# DS_PLUS1.net
KiCad netlist of a schematic drawn in EAGLE
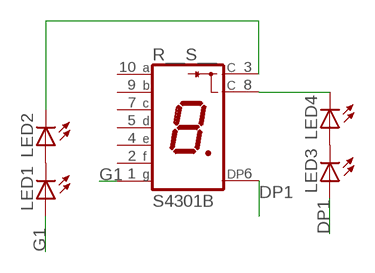
[diagram p0: schematic, sheet 1]

(export (version "E")
  (design (tool "Eeschema 10.0.6"))
  (components
    (comp (ref "LED1")
      (value "LEDCHIP-LED0603")
      (footprint "eagle-import:CHIP-LED0603")
      (libsource (lib "eagle-import") (part "LEDCHIP-LED0603"))
    )
    (comp (ref "LED2")
      (value "LEDCHIP-LED0603")
      (footprint "eagle-import:CHIP-LED0603")
      (libsource (lib "eagle-import") (part "LEDCHIP-LED0603"))
    )
    (comp (ref "LED3")
      (value "LEDCHIP-LED0603")
      (footprint "eagle-import:CHIP-LED0603")
      (libsource (lib "eagle-import") (part "LEDCHIP-LED0603"))
    )
    (comp (ref "LED4")
      (value "LEDCHIP-LED0603")
      (footprint "eagle-import:CHIP-LED0603")
      (libsource (lib "eagle-import") (part "LEDCHIP-LED0603"))
    )
    (comp (ref "R__S__")
      (value "S4301B")
      (footprint "eagle-import:S4301B")
      (libsource (lib "eagle-import") (part "S4301B"))
    )
  )
  (nets
    (net (code "1") (name "/DP1") (class "Default")
      (node (ref "LED3") (pin "A") (pinfunction "A_A") (pintype "passive"))
      (node (ref "R__S__") (pin "6") (pinfunction "DP_6") (pintype "passive"))
    )
    (net (code "2") (name "/G1") (class "Default")
      (node (ref "LED1") (pin "A") (pinfunction "A_A") (pintype "passive"))
      (node (ref "R__S__") (pin "1") (pinfunction "G_1") (pintype "passive"))
    )
    (net (code "3") (name "Net-(LED1-PadC)") (class "Default")
      (node (ref "LED1") (pin "C") (pinfunction "C_C") (pintype "passive"))
      (node (ref "LED2") (pin "A") (pinfunction "A_A") (pintype "passive"))
    )
    (net (code "4") (name "Net-(LED2-PadC)") (class "Default")
      (node (ref "LED2") (pin "C") (pinfunction "C_C") (pintype "passive"))
      (node (ref "R__S__") (pin "3") (pinfunction "C_3") (pintype "passive"))
    )
    (net (code "5") (name "Net-(LED3-PadC)") (class "Default")
      (node (ref "LED3") (pin "C") (pinfunction "C_C") (pintype "passive"))
      (node (ref "LED4") (pin "A") (pinfunction "A_A") (pintype "passive"))
    )
    (net (code "6") (name "Net-(LED4-PadC)") (class "Default")
      (node (ref "LED4") (pin "C") (pinfunction "C_C") (pintype "passive"))
      (node (ref "R__S__") (pin "8") (pinfunction "C_8") (pintype "passive"))
    )
    (net (code "7") (name "unconnected-(R__S__-A-Pad10)") (class "Default")
      (node (ref "R__S__") (pin "10") (pinfunction "A_10") (pintype "passive"))
    )
    (net (code "8") (name "unconnected-(R__S__-B-Pad9)") (class "Default")
      (node (ref "R__S__") (pin "9") (pinfunction "B_9") (pintype "passive"))
    )
    (net (code "9") (name "unconnected-(R__S__-C-Pad7)") (class "Default")
      (node (ref "R__S__") (pin "7") (pinfunction "C_7") (pintype "passive"))
    )
    (net (code "10") (name "unconnected-(R__S__-D-Pad5)") (class "Default")
      (node (ref "R__S__") (pin "5") (pinfunction "D_5") (pintype "passive"))
    )
    (net (code "11") (name "unconnected-(R__S__-E-Pad4)") (class "Default")
      (node (ref "R__S__") (pin "4") (pinfunction "E_4") (pintype "passive"))
    )
    (net (code "12") (name "unconnected-(R__S__-F-Pad2)") (class "Default")
      (node (ref "R__S__") (pin "2") (pinfunction "F_2") (pintype "passive"))
    )
  )
)
